# QSTL_MicroDSUB_Socket_FFC.net
KiCad netlist of a schematic drawn in Altium Designer
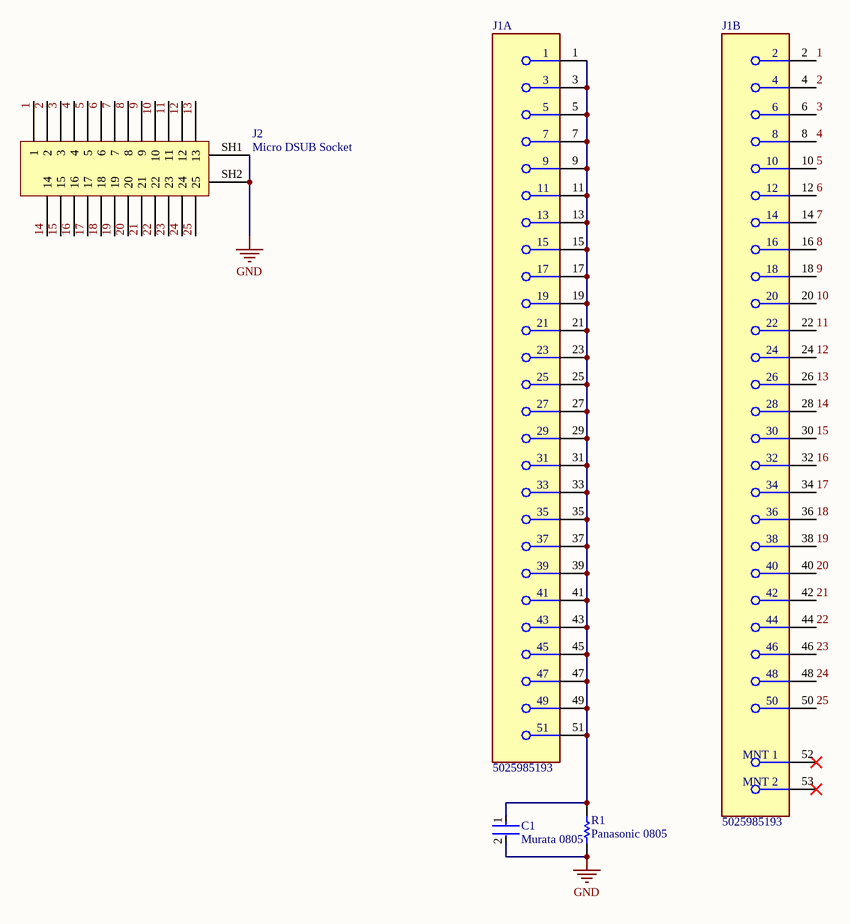
[diagram p0: QSTL_MicroDSUB_Socket_FFC.SchDoc]

(export (version "E")
  (design (tool "Eeschema 10.0.6"))
  (components
    (comp (ref "C1")
      (value "Murata 0805")
      (footprint "FP-GRM21B-0_15-MFG")
      (description "Chip Multilayer Ceramic Capacitors for General Purpose, 0805, 10uF, X7R, 15%, 10%, 10V")
      (fields (field (name "TOLERANCE") "10%"))
      (libsource (lib "Altium Content Vault") (part "b4654b650e69147ec39a6b967a45e02"))
    )
    (comp (ref "J1")
      (value "5025985193")
      (footprint "FP-5025985193-MFG")
      (description "CONN FPC 51POS 0.30MM R/A")
      (fields
        (field (name "OCTOPART") "https://octopart.com/502598-5193-molex-33127991")
        (field (name "MANUFACTURER") "Molex")
      )
      (libsource (lib "Altium Content Vault") (part "2f3a718b51213836fa913b7fc1fd98d"))
    )
    (comp (ref "J2")
      (value "Micro DSUB Socket")
      (footprint "380-025-213L001")
      (libsource (lib "QSTL_MicroDSUB_Socket_FFC") (part "380-025-213L001"))
    )
    (comp (ref "R1")
      (value "Panasonic 0805")
      (footprint "RESC2013X60X40LL20T25")
      (fields (field (name "MANUFACTURER") "Panasonic") (field (name "PART NUMBER") "ERA6AEB222V"))
      (libsource (lib "Altium Content Vault") (part "RES"))
    )
  )
  (nets
    (net (code "1") (name "/1") (class "Default")
      (node (ref "J1") (pin "2") (pinfunction "2_2") (pintype "passive"))
      (node (ref "J2") (pin "1") (pinfunction "1_1") (pintype "passive"))
    )
    (net (code "2") (name "/2") (class "Default")
      (node (ref "J1") (pin "4") (pinfunction "4_4") (pintype "passive"))
      (node (ref "J2") (pin "2") (pinfunction "2_2") (pintype "passive"))
    )
    (net (code "3") (name "/3") (class "Default")
      (node (ref "J1") (pin "6") (pinfunction "6_6") (pintype "passive"))
      (node (ref "J2") (pin "3") (pinfunction "3_3") (pintype "passive"))
    )
    (net (code "4") (name "/4") (class "Default")
      (node (ref "J1") (pin "8") (pinfunction "8_8") (pintype "passive"))
      (node (ref "J2") (pin "4") (pinfunction "4_4") (pintype "passive"))
    )
    (net (code "5") (name "/5") (class "Default")
      (node (ref "J1") (pin "10") (pinfunction "10_10") (pintype "passive"))
      (node (ref "J2") (pin "5") (pinfunction "5_5") (pintype "passive"))
    )
    (net (code "6") (name "/6") (class "Default")
      (node (ref "J1") (pin "12") (pinfunction "12_12") (pintype "passive"))
      (node (ref "J2") (pin "6") (pinfunction "6_6") (pintype "passive"))
    )
    (net (code "7") (name "/7") (class "Default")
      (node (ref "J1") (pin "14") (pinfunction "14_14") (pintype "passive"))
      (node (ref "J2") (pin "7") (pinfunction "7_7") (pintype "passive"))
    )
    (net (code "8") (name "/8") (class "Default")
      (node (ref "J1") (pin "16") (pinfunction "16_16") (pintype "passive"))
      (node (ref "J2") (pin "8") (pinfunction "8_8") (pintype "passive"))
    )
    (net (code "9") (name "/9") (class "Default")
      (node (ref "J1") (pin "18") (pinfunction "18_18") (pintype "passive"))
      (node (ref "J2") (pin "9") (pinfunction "9_9") (pintype "passive"))
    )
    (net (code "10") (name "/10") (class "Default")
      (node (ref "J1") (pin "20") (pinfunction "20_20") (pintype "passive"))
      (node (ref "J2") (pin "10") (pinfunction "10_10") (pintype "passive"))
    )
    (net (code "11") (name "/11") (class "Default")
      (node (ref "J1") (pin "22") (pinfunction "22_22") (pintype "passive"))
      (node (ref "J2") (pin "11") (pinfunction "11_11") (pintype "passive"))
    )
    (net (code "12") (name "/12") (class "Default")
      (node (ref "J1") (pin "24") (pinfunction "24_24") (pintype "passive"))
      (node (ref "J2") (pin "12") (pinfunction "12_12") (pintype "passive"))
    )
    (net (code "13") (name "/13") (class "Default")
      (node (ref "J1") (pin "26") (pinfunction "26_26") (pintype "passive"))
      (node (ref "J2") (pin "13") (pinfunction "13_13") (pintype "passive"))
    )
    (net (code "14") (name "/14") (class "Default")
      (node (ref "J1") (pin "28") (pinfunction "28_28") (pintype "passive"))
      (node (ref "J2") (pin "14") (pinfunction "14_14") (pintype "passive"))
    )
    (net (code "15") (name "/15") (class "Default")
      (node (ref "J1") (pin "30") (pinfunction "30_30") (pintype "passive"))
      (node (ref "J2") (pin "15") (pinfunction "15_15") (pintype "passive"))
    )
    (net (code "16") (name "/16") (class "Default")
      (node (ref "J1") (pin "32") (pinfunction "32_32") (pintype "passive"))
      (node (ref "J2") (pin "16") (pinfunction "16_16") (pintype "passive"))
    )
    (net (code "17") (name "/17") (class "Default")
      (node (ref "J1") (pin "34") (pinfunction "34_34") (pintype "passive"))
      (node (ref "J2") (pin "17") (pinfunction "17_17") (pintype "passive"))
    )
    (net (code "18") (name "/18") (class "Default")
      (node (ref "J1") (pin "36") (pinfunction "36_36") (pintype "passive"))
      (node (ref "J2") (pin "18") (pinfunction "18_18") (pintype "passive"))
    )
    (net (code "19") (name "/19") (class "Default")
      (node (ref "J1") (pin "38") (pinfunction "38_38") (pintype "passive"))
      (node (ref "J2") (pin "19") (pinfunction "19_19") (pintype "passive"))
    )
    (net (code "20") (name "/20") (class "Default")
      (node (ref "J1") (pin "40") (pinfunction "40_40") (pintype "passive"))
      (node (ref "J2") (pin "20") (pinfunction "20_20") (pintype "passive"))
    )
    (net (code "21") (name "/21") (class "Default")
      (node (ref "J1") (pin "42") (pinfunction "42_42") (pintype "passive"))
      (node (ref "J2") (pin "21") (pinfunction "21_21") (pintype "passive"))
    )
    (net (code "22") (name "/22") (class "Default")
      (node (ref "J1") (pin "44") (pinfunction "44_44") (pintype "passive"))
      (node (ref "J2") (pin "22") (pinfunction "22_22") (pintype "passive"))
    )
    (net (code "23") (name "/23") (class "Default")
      (node (ref "J1") (pin "46") (pinfunction "46_46") (pintype "passive"))
      (node (ref "J2") (pin "23") (pinfunction "23_23") (pintype "passive"))
    )
    (net (code "24") (name "/24") (class "Default")
      (node (ref "J1") (pin "48") (pinfunction "48_48") (pintype "passive"))
      (node (ref "J2") (pin "24") (pinfunction "24_24") (pintype "passive"))
    )
    (net (code "25") (name "/25") (class "Default")
      (node (ref "J1") (pin "50") (pinfunction "50_50") (pintype "passive"))
      (node (ref "J2") (pin "25") (pinfunction "25_25") (pintype "passive"))
    )
    (net (code "26") (name "GND") (class "Default")
      (node (ref "C1") (pin "2") (pinfunction "2_2") (pintype "passive"))
      (node (ref "J2") (pin "SH1") (pinfunction "SH1_SH1") (pintype "passive"))
      (node (ref "J2") (pin "SH2") (pinfunction "SH2_SH2") (pintype "passive"))
      (node (ref "R1") (pin "2") (pinfunction "2_2") (pintype "passive"))
    )
    (net (code "27") (name "Net-(C1-Pad1)") (class "Default")
      (node (ref "C1") (pin "1") (pinfunction "1_1") (pintype "passive"))
      (node (ref "J1") (pin "1") (pinfunction "1_1") (pintype "passive"))
      (node (ref "J1") (pin "11") (pinfunction "11_11") (pintype "passive"))
      (node (ref "J1") (pin "13") (pinfunction "13_13") (pintype "passive"))
      (node (ref "J1") (pin "15") (pinfunction "15_15") (pintype "passive"))
      (node (ref "J1") (pin "17") (pinfunction "17_17") (pintype "passive"))
      (node (ref "J1") (pin "19") (pinfunction "19_19") (pintype "passive"))
      (node (ref "J1") (pin "21") (pinfunction "21_21") (pintype "passive"))
      (node (ref "J1") (pin "23") (pinfunction "23_23") (pintype "passive"))
      (node (ref "J1") (pin "25") (pinfunction "25_25") (pintype "passive"))
      (node (ref "J1") (pin "27") (pinfunction "27_27") (pintype "passive"))
      (node (ref "J1") (pin "29") (pinfunction "29_29") (pintype "passive"))
      (node (ref "J1") (pin "3") (pinfunction "3_3") (pintype "passive"))
      (node (ref "J1") (pin "31") (pinfunction "31_31") (pintype "passive"))
      (node (ref "J1") (pin "33") (pinfunction "33_33") (pintype "passive"))
      (node (ref "J1") (pin "35") (pinfunction "35_35") (pintype "passive"))
      (node (ref "J1") (pin "37") (pinfunction "37_37") (pintype "passive"))
      (node (ref "J1") (pin "39") (pinfunction "39_39") (pintype "passive"))
      (node (ref "J1") (pin "41") (pinfunction "41_41") (pintype "passive"))
      (node (ref "J1") (pin "43") (pinfunction "43_43") (pintype "passive"))
      (node (ref "J1") (pin "45") (pinfunction "45_45") (pintype "passive"))
      (node (ref "J1") (pin "47") (pinfunction "47_47") (pintype "passive"))
      (node (ref "J1") (pin "49") (pinfunction "49_49") (pintype "passive"))
      (node (ref "J1") (pin "5") (pinfunction "5_5") (pintype "passive"))
      (node (ref "J1") (pin "51") (pinfunction "51_51") (pintype "passive"))
      (node (ref "J1") (pin "7") (pinfunction "7_7") (pintype "passive"))
      (node (ref "J1") (pin "9") (pinfunction "9_9") (pintype "passive"))
      (node (ref "R1") (pin "1") (pinfunction "1_1") (pintype "passive"))
    )
    (net (code "28") (name "unconnected-(J1B-MNT_1-Pad52)") (class "Default")
      (node (ref "J1") (pin "52") (pinfunction "MNT_1_52") (pintype "passive+no_connect"))
    )
    (net (code "29") (name "unconnected-(J1B-MNT_2-Pad53)") (class "Default")
      (node (ref "J1") (pin "53") (pinfunction "MNT_2_53") (pintype "passive+no_connect"))
    )
  )
)
